# serge_tkb_led_mod.net
KiCad netlist of a schematic drawn in EAGLE
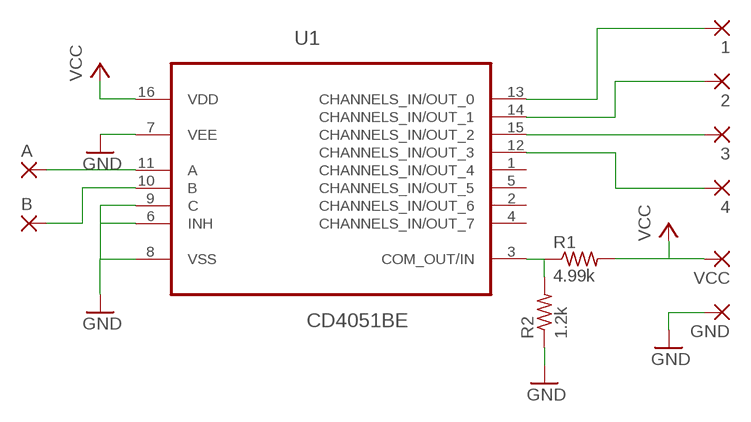
[diagram p0: schematic, sheet 1]

(export (version "E")
  (design (tool "Eeschema 10.0.6"))
  (components
    (comp (ref "1")
      (value "3,17/1,3")
      (footprint "eagle-import:3,17_1,3")
      (libsource (lib "eagle-import") (part "3,17/1,3"))
    )
    (comp (ref "2")
      (value "3,17/1,3")
      (footprint "eagle-import:3,17_1,3")
      (libsource (lib "eagle-import") (part "3,17/1,3"))
    )
    (comp (ref "3")
      (value "3,17/1,3")
      (footprint "eagle-import:3,17_1,3")
      (libsource (lib "eagle-import") (part "3,17/1,3"))
    )
    (comp (ref "4")
      (value "3,17/1,3")
      (footprint "eagle-import:3,17_1,3")
      (libsource (lib "eagle-import") (part "3,17/1,3"))
    )
    (comp (ref "A")
      (value "3,17/1,3")
      (footprint "eagle-import:3,17_1,3")
      (libsource (lib "eagle-import") (part "3,17/1,3"))
    )
    (comp (ref "B")
      (value "3,17/1,3")
      (footprint "eagle-import:3,17_1,3")
      (libsource (lib "eagle-import") (part "3,17/1,3"))
    )
    (comp (ref "GND")
      (value "3,17/1,3")
      (footprint "eagle-import:3,17_1,3")
      (libsource (lib "eagle-import") (part "3,17/1,3"))
    )
    (comp (ref "R1")
      (value "4.99k")
      (footprint "eagle-import:0207_10")
      (libsource (lib "eagle-import") (part "R-US_0207/10"))
    )
    (comp (ref "R2")
      (value "1.2k")
      (footprint "eagle-import:0207_10")
      (libsource (lib "eagle-import") (part "R-US_0207/10"))
    )
    (comp (ref "U1")
      (value "CD4051BE")
      (footprint "eagle-import:DIP254P762X508-16")
      (libsource (lib "eagle-import") (part "CD4051BE"))
    )
    (comp (ref "VCC")
      (value "3,17/1,3")
      (footprint "eagle-import:3,17_1,3")
      (libsource (lib "eagle-import") (part "3,17/1,3"))
    )
  )
  (nets
    (net (code "1") (name "GND") (class "Default")
      (node (ref "GND") (pin "1") (pinfunction "P_1") (pintype "passive"))
      (node (ref "R2") (pin "1") (pinfunction "1_1") (pintype "passive"))
      (node (ref "U1") (pin "6") (pinfunction "INH_6") (pintype "input"))
      (node (ref "U1") (pin "7") (pinfunction "VEE_7") (pintype "power_in"))
      (node (ref "U1") (pin "8") (pinfunction "VSS_8") (pintype "power_in"))
      (node (ref "U1") (pin "9") (pinfunction "C_9") (pintype "input"))
    )
    (net (code "2") (name "Net-(1-P)") (class "Default")
      (node (ref "1") (pin "1") (pinfunction "P_1") (pintype "passive"))
      (node (ref "U1") (pin "13") (pinfunction "CHANNELS_IN/OUT_0_13") (pintype "bidirectional"))
    )
    (net (code "3") (name "Net-(2-P)") (class "Default")
      (node (ref "2") (pin "1") (pinfunction "P_1") (pintype "passive"))
      (node (ref "U1") (pin "14") (pinfunction "CHANNELS_IN/OUT_1_14") (pintype "bidirectional"))
    )
    (net (code "4") (name "Net-(3-P)") (class "Default")
      (node (ref "3") (pin "1") (pinfunction "P_1") (pintype "passive"))
      (node (ref "U1") (pin "15") (pinfunction "CHANNELS_IN/OUT_2_15") (pintype "bidirectional"))
    )
    (net (code "5") (name "Net-(4-P)") (class "Default")
      (node (ref "4") (pin "1") (pinfunction "P_1") (pintype "passive"))
      (node (ref "U1") (pin "12") (pinfunction "CHANNELS_IN/OUT_3_12") (pintype "bidirectional"))
    )
    (net (code "6") (name "Net-(A-P)") (class "Default")
      (node (ref "A") (pin "1") (pinfunction "P_1") (pintype "passive"))
      (node (ref "U1") (pin "11") (pinfunction "A_11") (pintype "input"))
    )
    (net (code "7") (name "Net-(B-P)") (class "Default")
      (node (ref "B") (pin "1") (pinfunction "P_1") (pintype "passive"))
      (node (ref "U1") (pin "10") (pinfunction "B_10") (pintype "input"))
    )
    (net (code "8") (name "Net-(U1-COM_OUT{slash}IN)") (class "Default")
      (node (ref "R1") (pin "1") (pinfunction "1_1") (pintype "passive"))
      (node (ref "R2") (pin "2") (pinfunction "2_2") (pintype "passive"))
      (node (ref "U1") (pin "3") (pinfunction "COM_OUT/IN_3") (pintype "bidirectional"))
    )
    (net (code "9") (name "VCC") (class "Default")
      (node (ref "R1") (pin "2") (pinfunction "2_2") (pintype "passive"))
      (node (ref "U1") (pin "16") (pinfunction "VDD_16") (pintype "power_in"))
      (node (ref "VCC") (pin "1") (pinfunction "P_1") (pintype "passive"))
    )
    (net (code "10") (name "unconnected-(U1-CHANNELS_IN{slash}OUT_4-Pad1)") (class "Default")
      (node (ref "U1") (pin "1") (pinfunction "CHANNELS_IN/OUT_4_1") (pintype "bidirectional"))
    )
    (net (code "11") (name "unconnected-(U1-CHANNELS_IN{slash}OUT_5-Pad5)") (class "Default")
      (node (ref "U1") (pin "5") (pinfunction "CHANNELS_IN/OUT_5_5") (pintype "bidirectional"))
    )
    (net (code "12") (name "unconnected-(U1-CHANNELS_IN{slash}OUT_6-Pad2)") (class "Default")
      (node (ref "U1") (pin "2") (pinfunction "CHANNELS_IN/OUT_6_2") (pintype "bidirectional"))
    )
    (net (code "13") (name "unconnected-(U1-CHANNELS_IN{slash}OUT_7-Pad4)") (class "Default")
      (node (ref "U1") (pin "4") (pinfunction "CHANNELS_IN/OUT_7_4") (pintype "bidirectional"))
    )
  )
)
